# power.net
KiCad netlist of a schematic drawn in Altium Designer
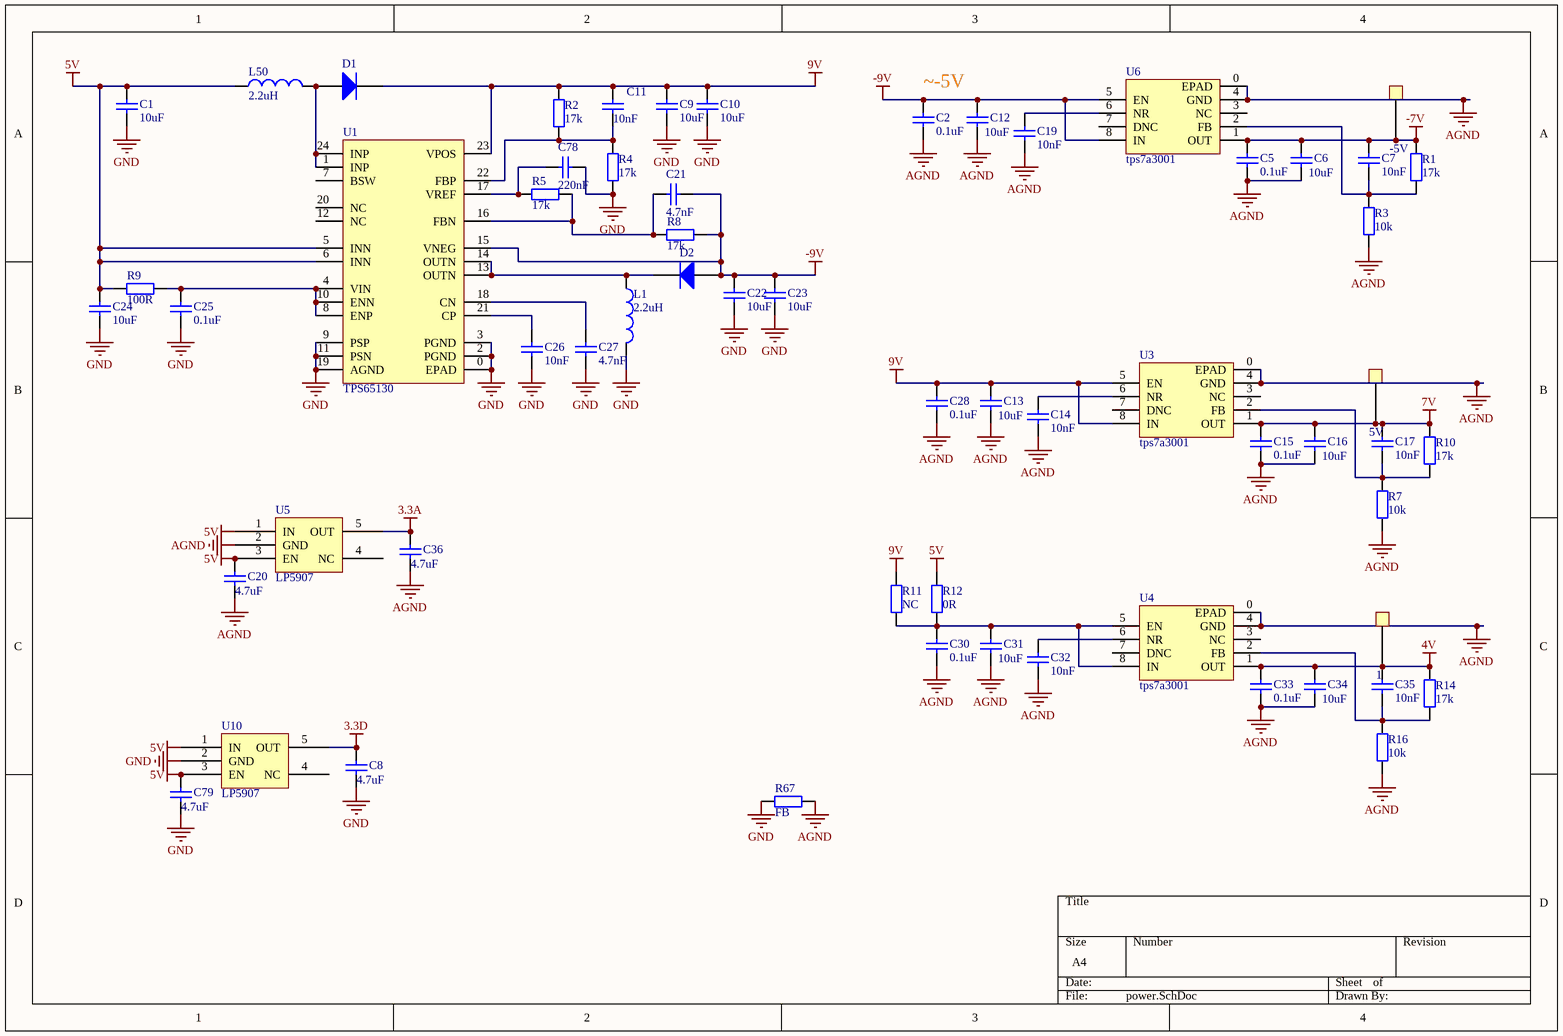
[diagram p0: power.SchDoc]

(export (version "E")
  (design (tool "Eeschema 10.0.6"))
  (components
    (comp (ref "-5V") (value "TestPad") (footprint "TestPad") (libsource (lib "sch") (part "TestPad")))
    (comp (ref "1") (value "TestPad") (footprint "TestPad") (libsource (lib "sch") (part "TestPad")))
    (comp (ref "5V") (value "TestPad") (footprint "TestPad") (libsource (lib "sch") (part "TestPad")))
    (comp (ref "C1")
      (value "10uF")
      (footprint "0603L")
      (description "Capacitor")
      (fields (field (name "PUBLISHER") "Altium Limited"))
      (libsource (lib "RTC6705") (part "Cap"))
    )
    (comp (ref "C2")
      (value "0.1uF")
      (footprint "0603L")
      (description "Capacitor")
      (fields (field (name "PUBLISHER") "Altium Limited"))
      (libsource (lib "RTC6705") (part "Cap"))
    )
    (comp (ref "C5")
      (value "0.1uF")
      (footprint "0603L")
      (description "Capacitor")
      (fields (field (name "PUBLISHER") "Altium Limited"))
      (libsource (lib "RTC6705") (part "Cap"))
    )
    (comp (ref "C6")
      (value "10uF")
      (footprint "0805")
      (description "Capacitor")
      (fields (field (name "PUBLISHER") "Altium Limited"))
      (libsource (lib "RTC6705") (part "Cap"))
    )
    (comp (ref "C7")
      (value "10nF")
      (footprint "0402")
      (description "Capacitor")
      (fields (field (name "PUBLISHER") "Altium Limited"))
      (libsource (lib "RTC6705") (part "Cap"))
    )
    (comp (ref "C8")
      (value "4.7uF")
      (footprint "0603L")
      (description "Capacitor")
      (fields (field (name "PUBLISHER") "Altium Limited"))
      (libsource (lib "RTC6705") (part "Cap"))
    )
    (comp (ref "C9")
      (value "10uF")
      (footprint "0603L")
      (description "Capacitor")
      (fields (field (name "PUBLISHER") "Altium Limited"))
      (libsource (lib "RTC6705") (part "Cap"))
    )
    (comp (ref "C10")
      (value "10uF")
      (footprint "0603L")
      (description "Capacitor")
      (fields (field (name "PUBLISHER") "Altium Limited"))
      (libsource (lib "RTC6705") (part "Cap"))
    )
    (comp (ref "C11")
      (value "10nF")
      (footprint "0402")
      (description "Capacitor")
      (fields (field (name "PUBLISHER") "Altium Limited"))
      (libsource (lib "RTC6705") (part "Cap"))
    )
    (comp (ref "C12")
      (value "10uF")
      (footprint "0805")
      (description "Capacitor")
      (fields (field (name "PUBLISHER") "Altium Limited"))
      (libsource (lib "RTC6705") (part "Cap"))
    )
    (comp (ref "C13")
      (value "10uF")
      (footprint "0805")
      (description "Capacitor")
      (fields (field (name "PUBLISHER") "Altium Limited"))
      (libsource (lib "RTC6705") (part "Cap"))
    )
    (comp (ref "C14")
      (value "10nF")
      (footprint "0402")
      (description "Capacitor")
      (fields (field (name "PUBLISHER") "Altium Limited"))
      (libsource (lib "RTC6705") (part "Cap"))
    )
    (comp (ref "C15")
      (value "0.1uF")
      (footprint "0603L")
      (description "Capacitor")
      (fields (field (name "PUBLISHER") "Altium Limited"))
      (libsource (lib "RTC6705") (part "Cap"))
    )
    (comp (ref "C16")
      (value "10uF")
      (footprint "0805")
      (description "Capacitor")
      (fields (field (name "PUBLISHER") "Altium Limited"))
      (libsource (lib "RTC6705") (part "Cap"))
    )
    (comp (ref "C17")
      (value "10nF")
      (footprint "0402")
      (description "Capacitor")
      (fields (field (name "PUBLISHER") "Altium Limited"))
      (libsource (lib "RTC6705") (part "Cap"))
    )
    (comp (ref "C19")
      (value "10nF")
      (footprint "0402")
      (description "Capacitor")
      (fields (field (name "PUBLISHER") "Altium Limited"))
      (libsource (lib "RTC6705") (part "Cap"))
    )
    (comp (ref "C20")
      (value "4.7uF")
      (footprint "0603L")
      (description "Capacitor")
      (fields (field (name "PUBLISHER") "Altium Limited"))
      (libsource (lib "RTC6705") (part "Cap"))
    )
    (comp (ref "C21")
      (value "4.7nF")
      (footprint "0402")
      (description "Capacitor")
      (fields (field (name "PUBLISHER") "Altium Limited"))
      (libsource (lib "RTC6705") (part "Cap"))
    )
    (comp (ref "C22")
      (value "10uF")
      (footprint "0603L")
      (description "Capacitor")
      (fields (field (name "PUBLISHER") "Altium Limited"))
      (libsource (lib "RTC6705") (part "Cap"))
    )
    (comp (ref "C23")
      (value "10uF")
      (footprint "0603L")
      (description "Capacitor")
      (fields (field (name "PUBLISHER") "Altium Limited"))
      (libsource (lib "RTC6705") (part "Cap"))
    )
    (comp (ref "C24")
      (value "10uF")
      (footprint "0603L")
      (description "Capacitor")
      (fields (field (name "PUBLISHER") "Altium Limited"))
      (libsource (lib "RTC6705") (part "Cap"))
    )
    (comp (ref "C25")
      (value "0.1uF")
      (footprint "0402")
      (description "Capacitor")
      (fields (field (name "PUBLISHER") "Altium Limited"))
      (libsource (lib "RTC6705") (part "Cap"))
    )
    (comp (ref "C26")
      (value "10nF")
      (footprint "0402")
      (description "Capacitor")
      (fields (field (name "PUBLISHER") "Altium Limited"))
      (libsource (lib "RTC6705") (part "Cap"))
    )
    (comp (ref "C27")
      (value "4.7nF")
      (footprint "0402")
      (description "Capacitor")
      (fields (field (name "PUBLISHER") "Altium Limited"))
      (libsource (lib "RTC6705") (part "Cap"))
    )
    (comp (ref "C28")
      (value "0.1uF")
      (footprint "0603L")
      (description "Capacitor")
      (fields (field (name "PUBLISHER") "Altium Limited"))
      (libsource (lib "RTC6705") (part "Cap"))
    )
    (comp (ref "C30")
      (value "0.1uF")
      (footprint "0603L")
      (description "Capacitor")
      (fields (field (name "PUBLISHER") "Altium Limited"))
      (libsource (lib "RTC6705") (part "Cap"))
    )
    (comp (ref "C31")
      (value "10uF")
      (footprint "0805")
      (description "Capacitor")
      (fields (field (name "PUBLISHER") "Altium Limited"))
      (libsource (lib "RTC6705") (part "Cap"))
    )
    (comp (ref "C32")
      (value "10nF")
      (footprint "0402")
      (description "Capacitor")
      (fields (field (name "PUBLISHER") "Altium Limited"))
      (libsource (lib "RTC6705") (part "Cap"))
    )
    (comp (ref "C33")
      (value "0.1uF")
      (footprint "0603L")
      (description "Capacitor")
      (fields (field (name "PUBLISHER") "Altium Limited"))
      (libsource (lib "RTC6705") (part "Cap"))
    )
    (comp (ref "C34")
      (value "10uF")
      (footprint "0805")
      (description "Capacitor")
      (fields (field (name "PUBLISHER") "Altium Limited"))
      (libsource (lib "RTC6705") (part "Cap"))
    )
    (comp (ref "C35")
      (value "10nF")
      (footprint "0402")
      (description "Capacitor")
      (fields (field (name "PUBLISHER") "Altium Limited"))
      (libsource (lib "RTC6705") (part "Cap"))
    )
    (comp (ref "C36")
      (value "4.7uF")
      (footprint "0603L")
      (description "Capacitor")
      (fields (field (name "PUBLISHER") "Altium Limited"))
      (libsource (lib "RTC6705") (part "Cap"))
    )
    (comp (ref "C78")
      (value "220nF")
      (footprint "0402")
      (description "Capacitor")
      (fields (field (name "PUBLISHER") "Altium Limited"))
      (libsource (lib "RTC6705") (part "Cap"))
    )
    (comp (ref "C79")
      (value "4.7uF")
      (footprint "0603L")
      (description "Capacitor")
      (fields (field (name "PUBLISHER") "Altium Limited"))
      (libsource (lib "RTC6705") (part "Cap"))
    )
    (comp (ref "D1")
      (value "~")
      (footprint "LC-SOD-323")
      (description "High Conductance Fast Diode")
      (fields (field (name "PUBLISHER") "Altium Limited"))
      (libsource (lib "Miscellaneous Devices") (part "Diode 1N4148"))
    )
    (comp (ref "D2")
      (value "~")
      (footprint "LC-SOD-323")
      (description "High Conductance Fast Diode")
      (fields (field (name "PUBLISHER") "Altium Limited"))
      (libsource (lib "Miscellaneous Devices") (part "Diode 1N4148"))
    )
    (comp (ref "L1")
      (value "2.2uH")
      (footprint "L4015")
      (description "Inductor")
      (fields (field (name "PUBLISHER") "Altium Limited"))
      (libsource (lib "Miscellaneous Devices") (part "Inductor"))
    )
    (comp (ref "L50")
      (value "2.2uH")
      (footprint "L4015")
      (description "Inductor")
      (fields (field (name "PUBLISHER") "Altium Limited"))
      (libsource (lib "Miscellaneous Devices") (part "Inductor"))
    )
    (comp (ref "R1")
      (value "17k")
      (footprint "0402")
      (description "Resistor")
      (fields (field (name "PUBLISHER") "Altium Limited"))
      (libsource (lib "RTC6705") (part "Res2"))
    )
    (comp (ref "R2")
      (value "17k")
      (footprint "0402")
      (description "Resistor")
      (fields (field (name "PUBLISHER") "Altium Limited"))
      (libsource (lib "RTC6705") (part "Res2"))
    )
    (comp (ref "R3")
      (value "10k")
      (footprint "0402")
      (description "Resistor")
      (fields (field (name "PUBLISHER") "Altium Limited"))
      (libsource (lib "RTC6705") (part "Res2"))
    )
    (comp (ref "R4")
      (value "17k")
      (footprint "0402")
      (description "Resistor")
      (fields (field (name "PUBLISHER") "Altium Limited"))
      (libsource (lib "RTC6705") (part "Res2"))
    )
    (comp (ref "R5")
      (value "17k")
      (footprint "0402")
      (description "Resistor")
      (fields (field (name "PUBLISHER") "Altium Limited"))
      (libsource (lib "") (part "Res2_2"))
    )
    (comp (ref "R7")
      (value "10k")
      (footprint "0402")
      (description "Resistor")
      (fields (field (name "PUBLISHER") "Altium Limited"))
      (libsource (lib "RTC6705") (part "Res2"))
    )
    (comp (ref "R8")
      (value "17k")
      (footprint "0402")
      (description "Resistor")
      (fields (field (name "PUBLISHER") "Altium Limited"))
      (libsource (lib "") (part "Res2_1"))
    )
    (comp (ref "R9")
      (value "100R")
      (footprint "0402")
      (description "Resistor")
      (fields (field (name "PUBLISHER") "Altium Limited"))
      (libsource (lib "") (part "Res2_2"))
    )
    (comp (ref "R10")
      (value "17k")
      (footprint "0402")
      (description "Resistor")
      (fields (field (name "PUBLISHER") "Altium Limited"))
      (libsource (lib "RTC6705") (part "Res2"))
    )
    (comp (ref "R11")
      (value "NC")
      (footprint "0402")
      (description "Resistor")
      (fields (field (name "PUBLISHER") "Altium Limited"))
      (libsource (lib "RTC6705") (part "Res2"))
    )
    (comp (ref "R12")
      (value "0R")
      (footprint "0402")
      (description "Resistor")
      (fields (field (name "PUBLISHER") "Altium Limited"))
      (libsource (lib "RTC6705") (part "Res2"))
    )
    (comp (ref "R14")
      (value "17k")
      (footprint "0402")
      (description "Resistor")
      (fields (field (name "PUBLISHER") "Altium Limited"))
      (libsource (lib "RTC6705") (part "Res2"))
    )
    (comp (ref "R16")
      (value "10k")
      (footprint "0402")
      (description "Resistor")
      (fields (field (name "PUBLISHER") "Altium Limited"))
      (libsource (lib "RTC6705") (part "Res2"))
    )
    (comp (ref "R67")
      (value "FB")
      (footprint "0603L")
      (description "Resistor")
      (fields (field (name "PUBLISHER") "Altium Limited"))
      (libsource (lib "") (part "Res2_2"))
    )
    (comp (ref "U1") (value "TPS65130") (footprint "TPS65130") (libsource (lib "sch") (part "TPS65130")))
    (comp (ref "U3")
      (value "tps7a3001")
      (footprint "MSOP8/VSSOP8+PAD")
      (libsource (lib "F4SDR") (part "tps7a3001"))
    )
    (comp (ref "U4")
      (value "tps7a3001")
      (footprint "MSOP8/VSSOP8+PAD")
      (libsource (lib "F4SDR") (part "tps7a3001"))
    )
    (comp (ref "U5") (value "LP5907") (footprint "SOT23-5") (libsource (lib "RTC6705") (part "LP5907")))
    (comp (ref "U6")
      (value "tps7a3001")
      (footprint "MSOP8/VSSOP8+PAD")
      (libsource (lib "F4SDR") (part "tps7a3001"))
    )
    (comp (ref "U10") (value "LP5907") (footprint "SOT23-5") (libsource (lib "RTC6705") (part "LP5907")))
  )
  (nets
    (net (code "1") (name "-7V") (class "Default")
      (node (ref "-5V") (pin "1") (pinfunction "3_1") (pintype "passive"))
      (node (ref "C5") (pin "1") (pinfunction "1_1") (pintype "passive"))
      (node (ref "C6") (pin "2") (pinfunction "2_2") (pintype "passive"))
      (node (ref "C7") (pin "1") (pinfunction "1_1") (pintype "passive"))
      (node (ref "R1") (pin "2") (pinfunction "2_2") (pintype "passive"))
      (node (ref "U6") (pin "1") (pinfunction "OUT_1") (pintype "passive"))
    )
    (net (code "2") (name "-9V") (class "Default")
      (node (ref "C12") (pin "2") (pinfunction "2_2") (pintype "passive"))
      (node (ref "C2") (pin "1") (pinfunction "1_1") (pintype "passive"))
      (node (ref "C21") (pin "2") (pinfunction "2_2") (pintype "passive"))
      (node (ref "C22") (pin "1") (pinfunction "1_1") (pintype "passive"))
      (node (ref "C23") (pin "1") (pinfunction "1_1") (pintype "passive"))
      (node (ref "D2") (pin "1") (pinfunction "A_1") (pintype "passive"))
      (node (ref "R8") (pin "2") (pinfunction "2_2") (pintype "passive"))
      (node (ref "U1") (pin "15") (pinfunction "VNEG_15") (pintype "passive"))
      (node (ref "U6") (pin "5") (pinfunction "EN_5") (pintype "passive"))
      (node (ref "U6") (pin "8") (pinfunction "IN_8") (pintype "passive"))
    )
    (net (code "3") (name "3.3A") (class "Default")
      (node (ref "C36") (pin "2") (pinfunction "2_2") (pintype "passive"))
      (node (ref "U5") (pin "5") (pinfunction "OUT_5") (pintype "passive"))
    )
    (net (code "4") (name "3.3D") (class "Default")
      (node (ref "C8") (pin "2") (pinfunction "2_2") (pintype "passive"))
      (node (ref "U10") (pin "5") (pinfunction "OUT_5") (pintype "passive"))
    )
    (net (code "5") (name "4V") (class "Default")
      (node (ref "1") (pin "1") (pinfunction "3_1") (pintype "passive"))
      (node (ref "C33") (pin "1") (pinfunction "1_1") (pintype "passive"))
      (node (ref "C34") (pin "2") (pinfunction "2_2") (pintype "passive"))
      (node (ref "C35") (pin "1") (pinfunction "1_1") (pintype "passive"))
      (node (ref "R14") (pin "2") (pinfunction "2_2") (pintype "passive"))
      (node (ref "U4") (pin "1") (pinfunction "OUT_1") (pintype "passive"))
    )
    (net (code "6") (name "5V") (class "Default")
      (node (ref "C1") (pin "1") (pinfunction "1_1") (pintype "passive"))
      (node (ref "C20") (pin "2") (pinfunction "2_2") (pintype "passive"))
      (node (ref "C24") (pin "1") (pinfunction "1_1") (pintype "passive"))
      (node (ref "C79") (pin "2") (pinfunction "2_2") (pintype "passive"))
      (node (ref "L50") (pin "1") (pinfunction "1_1") (pintype "passive"))
      (node (ref "R12") (pin "2") (pinfunction "2_2") (pintype "passive"))
      (node (ref "R9") (pin "2") (pinfunction "2_2") (pintype "passive"))
      (node (ref "U1") (pin "5") (pinfunction "INN_5") (pintype "passive"))
      (node (ref "U1") (pin "6") (pinfunction "INN_6") (pintype "passive"))
      (node (ref "U10") (pin "1") (pinfunction "IN_1") (pintype "passive"))
      (node (ref "U10") (pin "3") (pinfunction "EN_3") (pintype "passive"))
      (node (ref "U5") (pin "1") (pinfunction "IN_1") (pintype "passive"))
      (node (ref "U5") (pin "3") (pinfunction "EN_3") (pintype "passive"))
    )
    (net (code "7") (name "7V") (class "Default")
      (node (ref "5V") (pin "1") (pinfunction "3_1") (pintype "passive"))
      (node (ref "C15") (pin "1") (pinfunction "1_1") (pintype "passive"))
      (node (ref "C16") (pin "2") (pinfunction "2_2") (pintype "passive"))
      (node (ref "C17") (pin "1") (pinfunction "1_1") (pintype "passive"))
      (node (ref "R10") (pin "2") (pinfunction "2_2") (pintype "passive"))
      (node (ref "U3") (pin "1") (pinfunction "OUT_1") (pintype "passive"))
    )
    (net (code "8") (name "9V") (class "Default")
      (node (ref "C10") (pin "1") (pinfunction "1_1") (pintype "passive"))
      (node (ref "C11") (pin "1") (pinfunction "1_1") (pintype "passive"))
      (node (ref "C13") (pin "2") (pinfunction "2_2") (pintype "passive"))
      (node (ref "C28") (pin "1") (pinfunction "1_1") (pintype "passive"))
      (node (ref "C9") (pin "1") (pinfunction "1_1") (pintype "passive"))
      (node (ref "D1") (pin "2") (pinfunction "K_2") (pintype "passive"))
      (node (ref "R11") (pin "2") (pinfunction "2_2") (pintype "passive"))
      (node (ref "R2") (pin "2") (pinfunction "2_2") (pintype "passive"))
      (node (ref "U1") (pin "23") (pinfunction "VPOS_23") (pintype "passive"))
      (node (ref "U3") (pin "5") (pinfunction "EN_5") (pintype "passive"))
      (node (ref "U3") (pin "8") (pinfunction "IN_8") (pintype "passive"))
    )
    (net (code "9") (name "AGND") (class "Default")
      (node (ref "C12") (pin "1") (pinfunction "1_1") (pintype "passive"))
      (node (ref "C13") (pin "1") (pinfunction "1_1") (pintype "passive"))
      (node (ref "C14") (pin "2") (pinfunction "2_2") (pintype "passive"))
      (node (ref "C15") (pin "2") (pinfunction "2_2") (pintype "passive"))
      (node (ref "C16") (pin "1") (pinfunction "1_1") (pintype "passive"))
      (node (ref "C19") (pin "2") (pinfunction "2_2") (pintype "passive"))
      (node (ref "C2") (pin "2") (pinfunction "2_2") (pintype "passive"))
      (node (ref "C20") (pin "1") (pinfunction "1_1") (pintype "passive"))
      (node (ref "C28") (pin "2") (pinfunction "2_2") (pintype "passive"))
      (node (ref "C30") (pin "2") (pinfunction "2_2") (pintype "passive"))
      (node (ref "C31") (pin "1") (pinfunction "1_1") (pintype "passive"))
      (node (ref "C32") (pin "2") (pinfunction "2_2") (pintype "passive"))
      (node (ref "C33") (pin "2") (pinfunction "2_2") (pintype "passive"))
      (node (ref "C34") (pin "1") (pinfunction "1_1") (pintype "passive"))
      (node (ref "C36") (pin "1") (pinfunction "1_1") (pintype "passive"))
      (node (ref "C5") (pin "2") (pinfunction "2_2") (pintype "passive"))
      (node (ref "C6") (pin "1") (pinfunction "1_1") (pintype "passive"))
      (node (ref "R16") (pin "1") (pinfunction "1_1") (pintype "passive"))
      (node (ref "R3") (pin "1") (pinfunction "1_1") (pintype "passive"))
      (node (ref "R67") (pin "1") (pinfunction "1_1") (pintype "passive"))
      (node (ref "R7") (pin "1") (pinfunction "1_1") (pintype "passive"))
      (node (ref "U3") (pin "0") (pinfunction "EPAD_0") (pintype "passive"))
      (node (ref "U3") (pin "4") (pinfunction "GND_4") (pintype "passive"))
      (node (ref "U4") (pin "0") (pinfunction "EPAD_0") (pintype "passive"))
      (node (ref "U4") (pin "4") (pinfunction "GND_4") (pintype "passive"))
      (node (ref "U5") (pin "2") (pinfunction "GND_2") (pintype "passive"))
      (node (ref "U6") (pin "0") (pinfunction "EPAD_0") (pintype "passive"))
      (node (ref "U6") (pin "4") (pinfunction "GND_4") (pintype "passive"))
    )
    (net (code "10") (name "GND") (class "Default")
      (node (ref "C1") (pin "2") (pinfunction "2_2") (pintype "passive"))
      (node (ref "C10") (pin "2") (pinfunction "2_2") (pintype "passive"))
      (node (ref "C22") (pin "2") (pinfunction "2_2") (pintype "passive"))
      (node (ref "C23") (pin "2") (pinfunction "2_2") (pintype "passive"))
      (node (ref "C24") (pin "2") (pinfunction "2_2") (pintype "passive"))
      (node (ref "C25") (pin "2") (pinfunction "2_2") (pintype "passive"))
      (node (ref "C26") (pin "2") (pinfunction "2_2") (pintype "passive"))
      (node (ref "C27") (pin "2") (pinfunction "2_2") (pintype "passive"))
      (node (ref "C78") (pin "2") (pinfunction "2_2") (pintype "passive"))
      (node (ref "C79") (pin "1") (pinfunction "1_1") (pintype "passive"))
      (node (ref "C8") (pin "1") (pinfunction "1_1") (pintype "passive"))
      (node (ref "C9") (pin "2") (pinfunction "2_2") (pintype "passive"))
      (node (ref "L1") (pin "2") (pinfunction "2_2") (pintype "passive"))
      (node (ref "R4") (pin "1") (pinfunction "1_1") (pintype "passive"))
      (node (ref "R67") (pin "2") (pinfunction "2_2") (pintype "passive"))
      (node (ref "U1") (pin "0") (pinfunction "EPAD_0") (pintype "passive"))
      (node (ref "U1") (pin "11") (pinfunction "PSN_11") (pintype "passive"))
      (node (ref "U1") (pin "19") (pinfunction "AGND_19") (pintype "passive"))
      (node (ref "U1") (pin "2") (pinfunction "PGND_2") (pintype "passive"))
      (node (ref "U1") (pin "3") (pinfunction "PGND_3") (pintype "passive"))
      (node (ref "U1") (pin "9") (pinfunction "PSP_9") (pintype "passive"))
      (node (ref "U10") (pin "2") (pinfunction "GND_2") (pintype "passive"))
    )
    (net (code "11") (name "Net-(D1-A)") (class "Default")
      (node (ref "D1") (pin "1") (pinfunction "A_1") (pintype "passive"))
      (node (ref "L50") (pin "2") (pinfunction "2_2") (pintype "passive"))
      (node (ref "U1") (pin "1") (pinfunction "INP_1") (pintype "passive"))
      (node (ref "U1") (pin "24") (pinfunction "INP_24") (pintype "passive"))
    )
    (net (code "12") (name "Net-(D2-K)") (class "Default")
      (node (ref "D2") (pin "2") (pinfunction "K_2") (pintype "passive"))
      (node (ref "L1") (pin "1") (pinfunction "1_1") (pintype "passive"))
      (node (ref "U1") (pin "13") (pinfunction "OUTN_13") (pintype "passive"))
      (node (ref "U1") (pin "14") (pinfunction "OUTN_14") (pintype "passive"))
    )
    (net (code "13") (name "Net-(U1-CN)") (class "Default")
      (node (ref "C27") (pin "1") (pinfunction "1_1") (pintype "passive"))
      (node (ref "U1") (pin "18") (pinfunction "CN_18") (pintype "passive"))
    )
    (net (code "14") (name "Net-(U1-CP)") (class "Default")
      (node (ref "C26") (pin "1") (pinfunction "1_1") (pintype "passive"))
      (node (ref "U1") (pin "21") (pinfunction "CP_21") (pintype "passive"))
    )
    (net (code "15") (name "Net-(U1-ENN)") (class "Default")
      (node (ref "C25") (pin "1") (pinfunction "1_1") (pintype "passive"))
      (node (ref "R9") (pin "1") (pinfunction "1_1") (pintype "passive"))
      (node (ref "U1") (pin "10") (pinfunction "ENN_10") (pintype "passive"))
      (node (ref "U1") (pin "4") (pinfunction "VIN_4") (pintype "passive"))
      (node (ref "U1") (pin "8") (pinfunction "ENP_8") (pintype "passive"))
    )
    (net (code "16") (name "Net-(U1-FBN)") (class "Default")
      (node (ref "C21") (pin "1") (pinfunction "1_1") (pintype "passive"))
      (node (ref "R5") (pin "1") (pinfunction "1_1") (pintype "passive"))
      (node (ref "R8") (pin "1") (pinfunction "1_1") (pintype "passive"))
      (node (ref "U1") (pin "16") (pinfunction "FBN_16") (pintype "passive"))
    )
    (net (code "17") (name "Net-(U1-FBP)") (class "Default")
      (node (ref "C11") (pin "2") (pinfunction "2_2") (pintype "passive"))
      (node (ref "R2") (pin "1") (pinfunction "1_1") (pintype "passive"))
      (node (ref "R4") (pin "2") (pinfunction "2_2") (pintype "passive"))
      (node (ref "U1") (pin "22") (pinfunction "FBP_22") (pintype "passive"))
    )
    (net (code "18") (name "Net-(U1-VREF)") (class "Default")
      (node (ref "C78") (pin "1") (pinfunction "1_1") (pintype "passive"))
      (node (ref "R5") (pin "2") (pinfunction "2_2") (pintype "passive"))
      (node (ref "U1") (pin "17") (pinfunction "VREF_17") (pintype "passive"))
    )
    (net (code "19") (name "Net-(U3-FB)") (class "Default")
      (node (ref "C17") (pin "2") (pinfunction "2_2") (pintype "passive"))
      (node (ref "R10") (pin "1") (pinfunction "1_1") (pintype "passive"))
      (node (ref "R7") (pin "2") (pinfunction "2_2") (pintype "passive"))
      (node (ref "U3") (pin "2") (pinfunction "FB_2") (pintype "passive"))
    )
    (net (code "20") (name "Net-(U3-NR)") (class "Default")
      (node (ref "C14") (pin "1") (pinfunction "1_1") (pintype "passive"))
      (node (ref "U3") (pin "6") (pinfunction "NR_6") (pintype "passive"))
    )
    (net (code "21") (name "Net-(U4-EN)") (class "Default")
      (node (ref "C30") (pin "1") (pinfunction "1_1") (pintype "passive"))
      (node (ref "C31") (pin "2") (pinfunction "2_2") (pintype "passive"))
      (node (ref "R11") (pin "1") (pinfunction "1_1") (pintype "passive"))
      (node (ref "R12") (pin "1") (pinfunction "1_1") (pintype "passive"))
      (node (ref "U4") (pin "5") (pinfunction "EN_5") (pintype "passive"))
      (node (ref "U4") (pin "8") (pinfunction "IN_8") (pintype "passive"))
    )
    (net (code "22") (name "Net-(U4-FB)") (class "Default")
      (node (ref "C35") (pin "2") (pinfunction "2_2") (pintype "passive"))
      (node (ref "R14") (pin "1") (pinfunction "1_1") (pintype "passive"))
      (node (ref "R16") (pin "2") (pinfunction "2_2") (pintype "passive"))
      (node (ref "U4") (pin "2") (pinfunction "FB_2") (pintype "passive"))
    )
    (net (code "23") (name "Net-(U4-NR)") (class "Default")
      (node (ref "C32") (pin "1") (pinfunction "1_1") (pintype "passive"))
      (node (ref "U4") (pin "6") (pinfunction "NR_6") (pintype "passive"))
    )
    (net (code "24") (name "Net-(U6-FB)") (class "Default")
      (node (ref "C7") (pin "2") (pinfunction "2_2") (pintype "passive"))
      (node (ref "R1") (pin "1") (pinfunction "1_1") (pintype "passive"))
      (node (ref "R3") (pin "2") (pinfunction "2_2") (pintype "passive"))
      (node (ref "U6") (pin "2") (pinfunction "FB_2") (pintype "passive"))
    )
    (net (code "25") (name "Net-(U6-NR)") (class "Default")
      (node (ref "C19") (pin "1") (pinfunction "1_1") (pintype "passive"))
      (node (ref "U6") (pin "6") (pinfunction "NR_6") (pintype "passive"))
    )
    (net (code "26") (name "unconnected-(U1-BSW-Pad7)") (class "Default")
      (node (ref "U1") (pin "7") (pinfunction "BSW_7") (pintype "passive"))
    )
    (net (code "27") (name "unconnected-(U1-NC-Pad12)") (class "Default")
      (node (ref "U1") (pin "12") (pinfunction "NC_12") (pintype "passive"))
    )
    (net (code "28") (name "unconnected-(U1-NC-Pad20)") (class "Default")
      (node (ref "U1") (pin "20") (pinfunction "NC_20") (pintype "passive"))
    )
    (net (code "29") (name "unconnected-(U3-DNC-Pad7)") (class "Default")
      (node (ref "U3") (pin "7") (pinfunction "DNC_7") (pintype "passive"))
    )
    (net (code "30") (name "unconnected-(U3-NC-Pad3)") (class "Default")
      (node (ref "U3") (pin "3") (pinfunction "NC_3") (pintype "passive"))
    )
    (net (code "31") (name "unconnected-(U4-DNC-Pad7)") (class "Default")
      (node (ref "U4") (pin "7") (pinfunction "DNC_7") (pintype "passive"))
    )
    (net (code "32") (name "unconnected-(U4-NC-Pad3)") (class "Default")
      (node (ref "U4") (pin "3") (pinfunction "NC_3") (pintype "passive"))
    )
    (net (code "33") (name "unconnected-(U5-NC-Pad4)") (class "Default")
      (node (ref "U5") (pin "4") (pinfunction "NC_4") (pintype "passive"))
    )
    (net (code "34") (name "unconnected-(U6-DNC-Pad7)") (class "Default")
      (node (ref "U6") (pin "7") (pinfunction "DNC_7") (pintype "passive"))
    )
    (net (code "35") (name "unconnected-(U6-NC-Pad3)") (class "Default")
      (node (ref "U6") (pin "3") (pinfunction "NC_3") (pintype "passive"))
    )
    (net (code "36") (name "unconnected-(U10-NC-Pad4)") (class "Default")
      (node (ref "U10") (pin "4") (pinfunction "NC_4") (pintype "passive"))
    )
  )
)
